# Schematic_v1_1.net
KiCad netlist of a schematic drawn in EAGLE
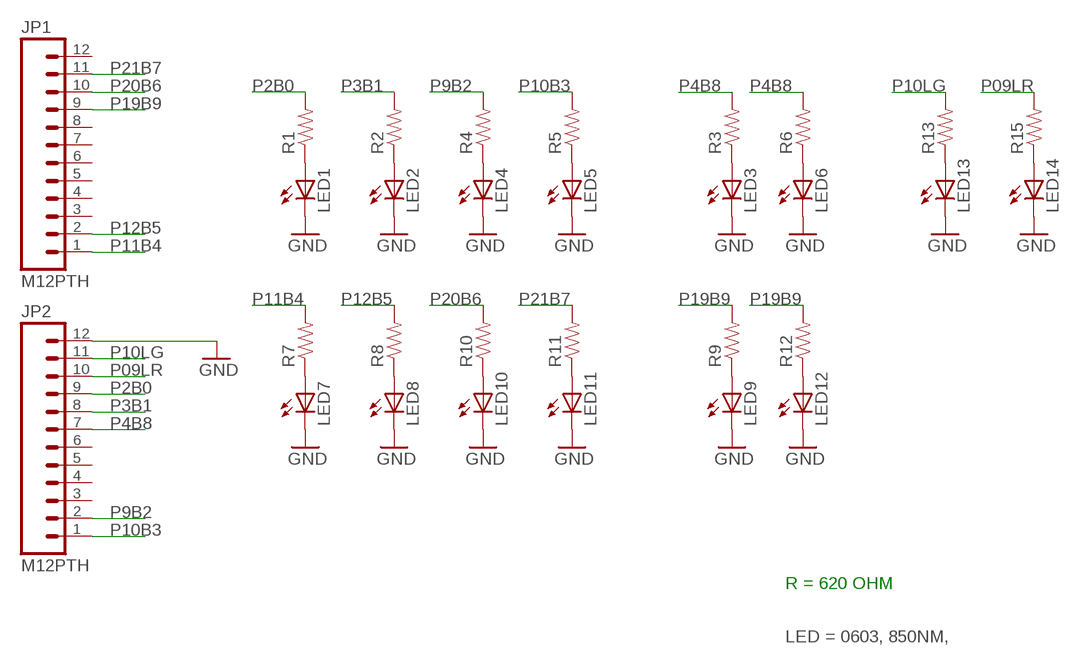
[diagram p0: schematic, sheet 1]

(export (version "E")
  (design (tool "Eeschema 10.0.6"))
  (components
    (comp (ref "JP1")
      (value "M12PTH")
      (footprint "eagle-import:1X12")
      (libsource (lib "eagle-import") (part "M12PTH"))
    )
    (comp (ref "JP2")
      (value "M12PTH")
      (footprint "eagle-import:1X12")
      (libsource (lib "eagle-import") (part "M12PTH"))
    )
    (comp (ref "LED1")
      (value "LEDCHIPLED_0603")
      (footprint "eagle-import:CHIPLED_0603")
      (libsource (lib "eagle-import") (part "LEDCHIPLED_0603"))
    )
    (comp (ref "LED2")
      (value "LEDCHIPLED_0603")
      (footprint "eagle-import:CHIPLED_0603")
      (libsource (lib "eagle-import") (part "LEDCHIPLED_0603"))
    )
    (comp (ref "LED3")
      (value "LEDCHIPLED_0603")
      (footprint "eagle-import:CHIPLED_0603")
      (libsource (lib "eagle-import") (part "LEDCHIPLED_0603"))
    )
    (comp (ref "LED4")
      (value "LEDCHIPLED_0603")
      (footprint "eagle-import:CHIPLED_0603")
      (libsource (lib "eagle-import") (part "LEDCHIPLED_0603"))
    )
    (comp (ref "LED5")
      (value "LEDCHIPLED_0603")
      (footprint "eagle-import:CHIPLED_0603")
      (libsource (lib "eagle-import") (part "LEDCHIPLED_0603"))
    )
    (comp (ref "LED6")
      (value "LEDCHIPLED_0603")
      (footprint "eagle-import:CHIPLED_0603")
      (libsource (lib "eagle-import") (part "LEDCHIPLED_0603"))
    )
    (comp (ref "LED7")
      (value "LEDCHIPLED_0603")
      (footprint "eagle-import:CHIPLED_0603")
      (libsource (lib "eagle-import") (part "LEDCHIPLED_0603"))
    )
    (comp (ref "LED8")
      (value "LEDCHIPLED_0603")
      (footprint "eagle-import:CHIPLED_0603")
      (libsource (lib "eagle-import") (part "LEDCHIPLED_0603"))
    )
    (comp (ref "LED9")
      (value "LEDCHIPLED_0603")
      (footprint "eagle-import:CHIPLED_0603")
      (libsource (lib "eagle-import") (part "LEDCHIPLED_0603"))
    )
    (comp (ref "LED10")
      (value "LEDCHIPLED_0603")
      (footprint "eagle-import:CHIPLED_0603")
      (libsource (lib "eagle-import") (part "LEDCHIPLED_0603"))
    )
    (comp (ref "LED11")
      (value "LEDCHIPLED_0603")
      (footprint "eagle-import:CHIPLED_0603")
      (libsource (lib "eagle-import") (part "LEDCHIPLED_0603"))
    )
    (comp (ref "LED12")
      (value "LEDCHIPLED_0603")
      (footprint "eagle-import:CHIPLED_0603")
      (libsource (lib "eagle-import") (part "LEDCHIPLED_0603"))
    )
    (comp (ref "LED13")
      (value "LEDCHIPLED_0603")
      (footprint "eagle-import:CHIPLED_0603")
      (libsource (lib "eagle-import") (part "LEDCHIPLED_0603"))
    )
    (comp (ref "LED14")
      (value "LEDCHIPLED_0603")
      (footprint "eagle-import:CHIPLED_0603")
      (libsource (lib "eagle-import") (part "LEDCHIPLED_0603"))
    )
    (comp (ref "R1")
      (value "RESISTOR0603-RES")
      (footprint "eagle-import:0603-RES")
      (libsource (lib "eagle-import") (part "RESISTOR0603-RES"))
    )
    (comp (ref "R2")
      (value "RESISTOR0603-RES")
      (footprint "eagle-import:0603-RES")
      (libsource (lib "eagle-import") (part "RESISTOR0603-RES"))
    )
    (comp (ref "R3")
      (value "RESISTOR0603-RES")
      (footprint "eagle-import:0603-RES")
      (libsource (lib "eagle-import") (part "RESISTOR0603-RES"))
    )
    (comp (ref "R4")
      (value "RESISTOR0603-RES")
      (footprint "eagle-import:0603-RES")
      (libsource (lib "eagle-import") (part "RESISTOR0603-RES"))
    )
    (comp (ref "R5")
      (value "RESISTOR0603-RES")
      (footprint "eagle-import:0603-RES")
      (libsource (lib "eagle-import") (part "RESISTOR0603-RES"))
    )
    (comp (ref "R6")
      (value "RESISTOR0603-RES")
      (footprint "eagle-import:0603-RES")
      (libsource (lib "eagle-import") (part "RESISTOR0603-RES"))
    )
    (comp (ref "R7")
      (value "RESISTOR0603-RES")
      (footprint "eagle-import:0603-RES")
      (libsource (lib "eagle-import") (part "RESISTOR0603-RES"))
    )
    (comp (ref "R8")
      (value "RESISTOR0603-RES")
      (footprint "eagle-import:0603-RES")
      (libsource (lib "eagle-import") (part "RESISTOR0603-RES"))
    )
    (comp (ref "R9")
      (value "RESISTOR0603-RES")
      (footprint "eagle-import:0603-RES")
      (libsource (lib "eagle-import") (part "RESISTOR0603-RES"))
    )
    (comp (ref "R10")
      (value "RESISTOR0603-RES")
      (footprint "eagle-import:0603-RES")
      (libsource (lib "eagle-import") (part "RESISTOR0603-RES"))
    )
    (comp (ref "R11")
      (value "RESISTOR0603-RES")
      (footprint "eagle-import:0603-RES")
      (libsource (lib "eagle-import") (part "RESISTOR0603-RES"))
    )
    (comp (ref "R12")
      (value "RESISTOR0603-RES")
      (footprint "eagle-import:0603-RES")
      (libsource (lib "eagle-import") (part "RESISTOR0603-RES"))
    )
    (comp (ref "R13")
      (value "RESISTOR0603-RES")
      (footprint "eagle-import:0603-RES")
      (libsource (lib "eagle-import") (part "RESISTOR0603-RES"))
    )
    (comp (ref "R15")
      (value "RESISTOR0603-RES")
      (footprint "eagle-import:0603-RES")
      (libsource (lib "eagle-import") (part "RESISTOR0603-RES"))
    )
  )
  (nets
    (net (code "1") (name "/P2B0") (class "Default")
      (node (ref "JP2") (pin "9") (pinfunction "9_9") (pintype "passive"))
      (node (ref "R1") (pin "2") (pinfunction "2_2") (pintype "passive"))
    )
    (net (code "2") (name "/P3B1") (class "Default")
      (node (ref "JP2") (pin "8") (pinfunction "8_8") (pintype "passive"))
      (node (ref "R2") (pin "2") (pinfunction "2_2") (pintype "passive"))
    )
    (net (code "3") (name "/P4B8") (class "Default")
      (node (ref "JP2") (pin "7") (pinfunction "7_7") (pintype "passive"))
      (node (ref "R3") (pin "2") (pinfunction "2_2") (pintype "passive"))
      (node (ref "R6") (pin "2") (pinfunction "2_2") (pintype "passive"))
    )
    (net (code "4") (name "/P9B2") (class "Default")
      (node (ref "JP2") (pin "2") (pinfunction "2_2") (pintype "passive"))
      (node (ref "R4") (pin "2") (pinfunction "2_2") (pintype "passive"))
    )
    (net (code "5") (name "/P09LR") (class "Default")
      (node (ref "JP2") (pin "10") (pinfunction "10_10") (pintype "passive"))
      (node (ref "R15") (pin "2") (pinfunction "2_2") (pintype "passive"))
    )
    (net (code "6") (name "/P10B3") (class "Default")
      (node (ref "JP2") (pin "1") (pinfunction "1_1") (pintype "passive"))
      (node (ref "R5") (pin "2") (pinfunction "2_2") (pintype "passive"))
    )
    (net (code "7") (name "/P10LG") (class "Default")
      (node (ref "JP2") (pin "11") (pinfunction "11_11") (pintype "passive"))
      (node (ref "R13") (pin "2") (pinfunction "2_2") (pintype "passive"))
    )
    (net (code "8") (name "/P11B4") (class "Default")
      (node (ref "JP1") (pin "1") (pinfunction "1_1") (pintype "passive"))
      (node (ref "R7") (pin "2") (pinfunction "2_2") (pintype "passive"))
    )
    (net (code "9") (name "/P12B5") (class "Default")
      (node (ref "JP1") (pin "2") (pinfunction "2_2") (pintype "passive"))
      (node (ref "R8") (pin "2") (pinfunction "2_2") (pintype "passive"))
    )
    (net (code "10") (name "/P19B9") (class "Default")
      (node (ref "JP1") (pin "9") (pinfunction "9_9") (pintype "passive"))
      (node (ref "R12") (pin "2") (pinfunction "2_2") (pintype "passive"))
      (node (ref "R9") (pin "2") (pinfunction "2_2") (pintype "passive"))
    )
    (net (code "11") (name "/P20B6") (class "Default")
      (node (ref "JP1") (pin "10") (pinfunction "10_10") (pintype "passive"))
      (node (ref "R10") (pin "2") (pinfunction "2_2") (pintype "passive"))
    )
    (net (code "12") (name "/P21B7") (class "Default")
      (node (ref "JP1") (pin "11") (pinfunction "11_11") (pintype "passive"))
      (node (ref "R11") (pin "2") (pinfunction "2_2") (pintype "passive"))
    )
    (net (code "13") (name "GND") (class "Default")
      (node (ref "JP2") (pin "12") (pinfunction "12_12") (pintype "passive"))
      (node (ref "LED1") (pin "C") (pinfunction "C_C") (pintype "passive"))
      (node (ref "LED10") (pin "C") (pinfunction "C_C") (pintype "passive"))
      (node (ref "LED11") (pin "C") (pinfunction "C_C") (pintype "passive"))
      (node (ref "LED12") (pin "C") (pinfunction "C_C") (pintype "passive"))
      (node (ref "LED13") (pin "C") (pinfunction "C_C") (pintype "passive"))
      (node (ref "LED14") (pin "C") (pinfunction "C_C") (pintype "passive"))
      (node (ref "LED2") (pin "C") (pinfunction "C_C") (pintype "passive"))
      (node (ref "LED3") (pin "C") (pinfunction "C_C") (pintype "passive"))
      (node (ref "LED4") (pin "C") (pinfunction "C_C") (pintype "passive"))
      (node (ref "LED5") (pin "C") (pinfunction "C_C") (pintype "passive"))
      (node (ref "LED6") (pin "C") (pinfunction "C_C") (pintype "passive"))
      (node (ref "LED7") (pin "C") (pinfunction "C_C") (pintype "passive"))
      (node (ref "LED8") (pin "C") (pinfunction "C_C") (pintype "passive"))
      (node (ref "LED9") (pin "C") (pinfunction "C_C") (pintype "passive"))
    )
    (net (code "14") (name "Net-(LED1-PadA)") (class "Default")
      (node (ref "LED1") (pin "A") (pinfunction "A_A") (pintype "passive"))
      (node (ref "R1") (pin "1") (pinfunction "1_1") (pintype "passive"))
    )
    (net (code "15") (name "Net-(LED2-PadA)") (class "Default")
      (node (ref "LED2") (pin "A") (pinfunction "A_A") (pintype "passive"))
      (node (ref "R2") (pin "1") (pinfunction "1_1") (pintype "passive"))
    )
    (net (code "16") (name "Net-(LED3-PadA)") (class "Default")
      (node (ref "LED3") (pin "A") (pinfunction "A_A") (pintype "passive"))
      (node (ref "R3") (pin "1") (pinfunction "1_1") (pintype "passive"))
    )
    (net (code "17") (name "Net-(LED4-PadA)") (class "Default")
      (node (ref "LED4") (pin "A") (pinfunction "A_A") (pintype "passive"))
      (node (ref "R4") (pin "1") (pinfunction "1_1") (pintype "passive"))
    )
    (net (code "18") (name "Net-(LED5-PadA)") (class "Default")
      (node (ref "LED5") (pin "A") (pinfunction "A_A") (pintype "passive"))
      (node (ref "R5") (pin "1") (pinfunction "1_1") (pintype "passive"))
    )
    (net (code "19") (name "Net-(LED6-PadA)") (class "Default")
      (node (ref "LED6") (pin "A") (pinfunction "A_A") (pintype "passive"))
      (node (ref "R6") (pin "1") (pinfunction "1_1") (pintype "passive"))
    )
    (net (code "20") (name "Net-(LED7-PadA)") (class "Default")
      (node (ref "LED7") (pin "A") (pinfunction "A_A") (pintype "passive"))
      (node (ref "R7") (pin "1") (pinfunction "1_1") (pintype "passive"))
    )
    (net (code "21") (name "Net-(LED8-PadA)") (class "Default")
      (node (ref "LED8") (pin "A") (pinfunction "A_A") (pintype "passive"))
      (node (ref "R8") (pin "1") (pinfunction "1_1") (pintype "passive"))
    )
    (net (code "22") (name "Net-(LED9-PadA)") (class "Default")
      (node (ref "LED9") (pin "A") (pinfunction "A_A") (pintype "passive"))
      (node (ref "R9") (pin "1") (pinfunction "1_1") (pintype "passive"))
    )
    (net (code "23") (name "Net-(LED10-PadA)") (class "Default")
      (node (ref "LED10") (pin "A") (pinfunction "A_A") (pintype "passive"))
      (node (ref "R10") (pin "1") (pinfunction "1_1") (pintype "passive"))
    )
    (net (code "24") (name "Net-(LED11-PadA)") (class "Default")
      (node (ref "LED11") (pin "A") (pinfunction "A_A") (pintype "passive"))
      (node (ref "R11") (pin "1") (pinfunction "1_1") (pintype "passive"))
    )
    (net (code "25") (name "Net-(LED12-PadA)") (class "Default")
      (node (ref "LED12") (pin "A") (pinfunction "A_A") (pintype "passive"))
      (node (ref "R12") (pin "1") (pinfunction "1_1") (pintype "passive"))
    )
    (net (code "26") (name "Net-(LED13-PadA)") (class "Default")
      (node (ref "LED13") (pin "A") (pinfunction "A_A") (pintype "passive"))
      (node (ref "R13") (pin "1") (pinfunction "1_1") (pintype "passive"))
    )
    (net (code "27") (name "Net-(LED14-PadA)") (class "Default")
      (node (ref "LED14") (pin "A") (pinfunction "A_A") (pintype "passive"))
      (node (ref "R15") (pin "1") (pinfunction "1_1") (pintype "passive"))
    )
    (net (code "28") (name "unconnected-(JP1-Pad3)") (class "Default")
      (node (ref "JP1") (pin "3") (pinfunction "3_3") (pintype "passive"))
    )
    (net (code "29") (name "unconnected-(JP1-Pad4)") (class "Default")
      (node (ref "JP1") (pin "4") (pinfunction "4_4") (pintype "passive"))
    )
    (net (code "30") (name "unconnected-(JP1-Pad5)") (class "Default")
      (node (ref "JP1") (pin "5") (pinfunction "5_5") (pintype "passive"))
    )
    (net (code "31") (name "unconnected-(JP1-Pad6)") (class "Default")
      (node (ref "JP1") (pin "6") (pinfunction "6_6") (pintype "passive"))
    )
    (net (code "32") (name "unconnected-(JP1-Pad7)") (class "Default")
      (node (ref "JP1") (pin "7") (pinfunction "7_7") (pintype "passive"))
    )
    (net (code "33") (name "unconnected-(JP1-Pad8)") (class "Default")
      (node (ref "JP1") (pin "8") (pinfunction "8_8") (pintype "passive"))
    )
    (net (code "34") (name "unconnected-(JP1-Pad12)") (class "Default")
      (node (ref "JP1") (pin "12") (pinfunction "12_12") (pintype "passive"))
    )
    (net (code "35") (name "unconnected-(JP2-Pad3)") (class "Default")
      (node (ref "JP2") (pin "3") (pinfunction "3_3") (pintype "passive"))
    )
    (net (code "36") (name "unconnected-(JP2-Pad4)") (class "Default")
      (node (ref "JP2") (pin "4") (pinfunction "4_4") (pintype "passive"))
    )
    (net (code "37") (name "unconnected-(JP2-Pad5)") (class "Default")
      (node (ref "JP2") (pin "5") (pinfunction "5_5") (pintype "passive"))
    )
    (net (code "38") (name "unconnected-(JP2-Pad6)") (class "Default")
      (node (ref "JP2") (pin "6") (pinfunction "6_6") (pintype "passive"))
    )
  )
)
